# Thermometers.net
KiCad netlist of a schematic drawn in Altium Designer
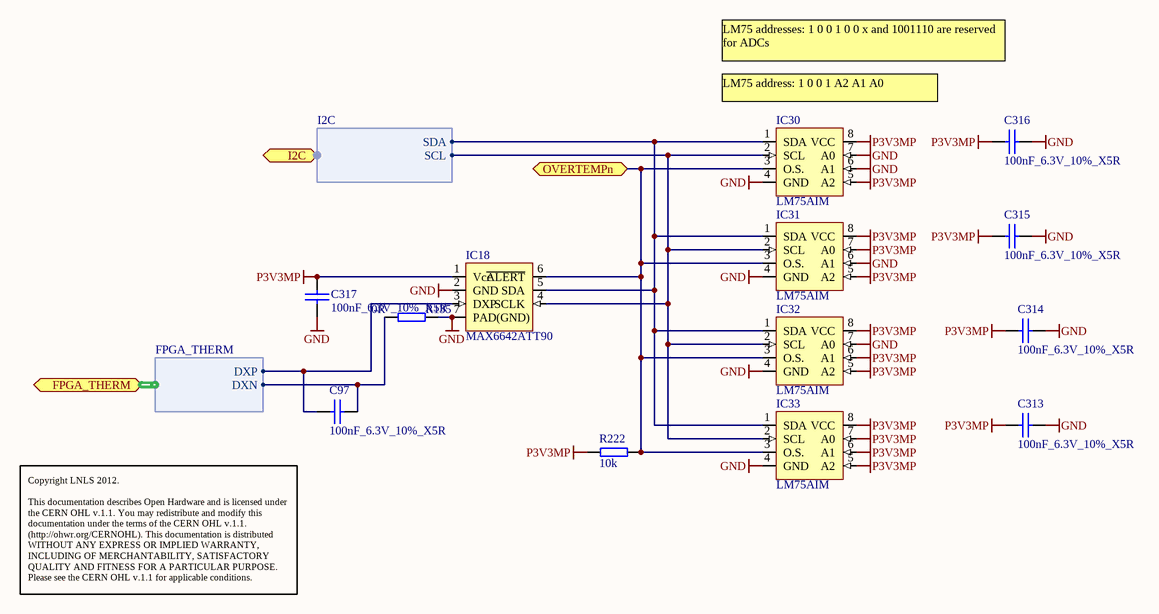
[diagram p0: Thermometers.SchDoc]

(export (version "E")
  (design (tool "Eeschema 10.0.6"))
  (components
    (comp (ref "C97")
      (value "100nF_6.3V_10%_X5R")
      (footprint "0201C")
      (description "Capacitor SMD")
      (libsource (lib "LIBRARY_SCH") (part "CAP_SMD_0201"))
    )
    (comp (ref "C313")
      (value "100nF_6.3V_10%_X5R")
      (footprint "0201C")
      (description "Capacitor SMD")
      (libsource (lib "LIBRARY_SCH") (part "CAP_SMD_0201"))
    )
    (comp (ref "C314")
      (value "100nF_6.3V_10%_X5R")
      (footprint "0201C")
      (description "Capacitor SMD")
      (libsource (lib "LIBRARY_SCH") (part "CAP_SMD_0201"))
    )
    (comp (ref "C315")
      (value "100nF_6.3V_10%_X5R")
      (footprint "0201C")
      (description "Capacitor SMD")
      (libsource (lib "LIBRARY_SCH") (part "CAP_SMD_0201"))
    )
    (comp (ref "C316")
      (value "100nF_6.3V_10%_X5R")
      (footprint "0201C")
      (description "Capacitor SMD")
      (libsource (lib "LIBRARY_SCH") (part "CAP_SMD_0201"))
    )
    (comp (ref "C317")
      (value "100nF_6.3V_10%_X5R")
      (footprint "0201C")
      (description "Capacitor SMD")
      (libsource (lib "LIBRARY_SCH") (part "CAP_SMD_0201"))
    )
    (comp (ref "IC18")
      (value "MAX6642ATT90")
      (footprint "TFDN6")
      (description "±1°C, SMBus- Remote/Local Temperature Sensor with Overtemperature Alarm")
      (libsource (lib "LIBRARY_SCH") (part "SENS_MAX6642"))
    )
    (comp (ref "IC30")
      (value "LM75AIM")
      (footprint "SOIC127P600X175-8N")
      (description "I2C temperature sensor")
      (libsource (lib "LIBRARY_SCH") (part "SENS_LM75"))
    )
    (comp (ref "IC31")
      (value "LM75AIM")
      (footprint "SOIC127P600X175-8N")
      (description "I2C temperature sensor")
      (libsource (lib "LIBRARY_SCH") (part "SENS_LM75"))
    )
    (comp (ref "IC32")
      (value "LM75AIM")
      (footprint "SOIC127P600X175-8N")
      (description "I2C temperature sensor")
      (libsource (lib "LIBRARY_SCH") (part "SENS_LM75"))
    )
    (comp (ref "IC33")
      (value "LM75AIM")
      (footprint "SOIC127P600X175-8N")
      (description "I2C temperature sensor")
      (libsource (lib "LIBRARY_SCH") (part "SENS_LM75"))
    )
    (comp (ref "R135")
      (value "0R")
      (footprint "0402R")
      (description "SMD Resistor")
      (libsource (lib "LIBRARY_SCH") (part "RES_0402"))
    )
    (comp (ref "R222")
      (value "10k")
      (footprint "0402R")
      (description "SMD Resistor")
      (libsource (lib "*") (part "RES_SMD"))
    )
  )
  (nets
    (net (code "3") (name "/OVERTEMPn") (class "Default")
      (node (ref "IC18") (pin "6") (pinfunction "~{ALERT}_6") (pintype "open_collector"))
      (node (ref "IC30") (pin "3") (pinfunction "O.S._3") (pintype "open_collector"))
      (node (ref "IC31") (pin "3") (pinfunction "O.S._3") (pintype "open_collector"))
      (node (ref "IC32") (pin "3") (pinfunction "O.S._3") (pintype "open_collector"))
      (node (ref "IC33") (pin "3") (pinfunction "O.S._3") (pintype "open_collector"))
      (node (ref "R222") (pin "2") (pinfunction "2_2") (pintype "passive"))
    )
    (net (code "6") (name "GND") (class "Default")
      (node (ref "C313") (pin "2") (pinfunction "2_2") (pintype "passive"))
      (node (ref "C314") (pin "2") (pinfunction "2_2") (pintype "passive"))
      (node (ref "C315") (pin "2") (pinfunction "2_2") (pintype "passive"))
      (node (ref "C316") (pin "2") (pinfunction "2_2") (pintype "passive"))
      (node (ref "C317") (pin "2") (pinfunction "2_2") (pintype "passive"))
      (node (ref "IC18") (pin "2") (pinfunction "GND_2") (pintype "power_in"))
      (node (ref "IC18") (pin "7") (pinfunction "PAD(GND)_7") (pintype "power_in"))
      (node (ref "IC30") (pin "4") (pinfunction "GND_4") (pintype "power_in"))
      (node (ref "IC30") (pin "6") (pinfunction "A1_6") (pintype "input"))
      (node (ref "IC30") (pin "7") (pinfunction "A0_7") (pintype "input"))
      (node (ref "IC31") (pin "4") (pinfunction "GND_4") (pintype "power_in"))
      (node (ref "IC31") (pin "6") (pinfunction "A1_6") (pintype "input"))
      (node (ref "IC32") (pin "4") (pinfunction "GND_4") (pintype "power_in"))
      (node (ref "IC32") (pin "7") (pinfunction "A0_7") (pintype "input"))
      (node (ref "IC33") (pin "4") (pinfunction "GND_4") (pintype "power_in"))
      (node (ref "R135") (pin "2") (pinfunction "2_2") (pintype "passive"))
    )
    (net (code "7") (name "Net-(C97-Pad2)") (class "Default")
      (node (ref "C97") (pin "2") (pinfunction "2_2") (pintype "passive"))
      (node (ref "R135") (pin "1") (pinfunction "1_1") (pintype "passive"))
    )
    (net (code "8") (name "Net-(IC18-DXP)") (class "Default")
      (node (ref "C97") (pin "1") (pinfunction "1_1") (pintype "passive"))
      (node (ref "IC18") (pin "3") (pinfunction "DXP_3") (pintype "input"))
    )
    (net (code "9") (name "Net-(IC18-SCLK)") (class "Default")
      (node (ref "IC18") (pin "4") (pinfunction "SCLK_4") (pintype "input"))
      (node (ref "IC30") (pin "2") (pinfunction "SCL_2") (pintype "input"))
      (node (ref "IC31") (pin "2") (pinfunction "SCL_2") (pintype "input"))
      (node (ref "IC32") (pin "2") (pinfunction "SCL_2") (pintype "input"))
      (node (ref "IC33") (pin "2") (pinfunction "SCL_2") (pintype "input"))
    )
    (net (code "10") (name "Net-(IC18-SDA)") (class "Default")
      (node (ref "IC18") (pin "5") (pinfunction "SDA_5") (pintype "bidirectional"))
      (node (ref "IC30") (pin "1") (pinfunction "SDA_1") (pintype "bidirectional"))
      (node (ref "IC31") (pin "1") (pinfunction "SDA_1") (pintype "bidirectional"))
      (node (ref "IC32") (pin "1") (pinfunction "SDA_1") (pintype "bidirectional"))
      (node (ref "IC33") (pin "1") (pinfunction "SDA_1") (pintype "bidirectional"))
    )
    (net (code "11") (name "P3V3MP") (class "Default")
      (node (ref "C313") (pin "1") (pinfunction "1_1") (pintype "passive"))
      (node (ref "C314") (pin "1") (pinfunction "1_1") (pintype "passive"))
      (node (ref "C315") (pin "1") (pinfunction "1_1") (pintype "passive"))
      (node (ref "C316") (pin "1") (pinfunction "1_1") (pintype "passive"))
      (node (ref "C317") (pin "1") (pinfunction "1_1") (pintype "passive"))
      (node (ref "IC18") (pin "1") (pinfunction "Vcc_1") (pintype "power_in"))
      (node (ref "IC30") (pin "5") (pinfunction "A2_5") (pintype "input"))
      (node (ref "IC30") (pin "8") (pinfunction "VCC_8") (pintype "power_in"))
      (node (ref "IC31") (pin "5") (pinfunction "A2_5") (pintype "input"))
      (node (ref "IC31") (pin "7") (pinfunction "A0_7") (pintype "input"))
      (node (ref "IC31") (pin "8") (pinfunction "VCC_8") (pintype "power_in"))
      (node (ref "IC32") (pin "5") (pinfunction "A2_5") (pintype "input"))
      (node (ref "IC32") (pin "6") (pinfunction "A1_6") (pintype "input"))
      (node (ref "IC32") (pin "8") (pinfunction "VCC_8") (pintype "power_in"))
      (node (ref "IC33") (pin "5") (pinfunction "A2_5") (pintype "input"))
      (node (ref "IC33") (pin "6") (pinfunction "A1_6") (pintype "input"))
      (node (ref "IC33") (pin "7") (pinfunction "A0_7") (pintype "input"))
      (node (ref "IC33") (pin "8") (pinfunction "VCC_8") (pintype "power_in"))
      (node (ref "R222") (pin "1") (pinfunction "1_1") (pintype "passive"))
    )
  )
)
